# controller.net
KiCad netlist of a schematic drawn in EAGLE
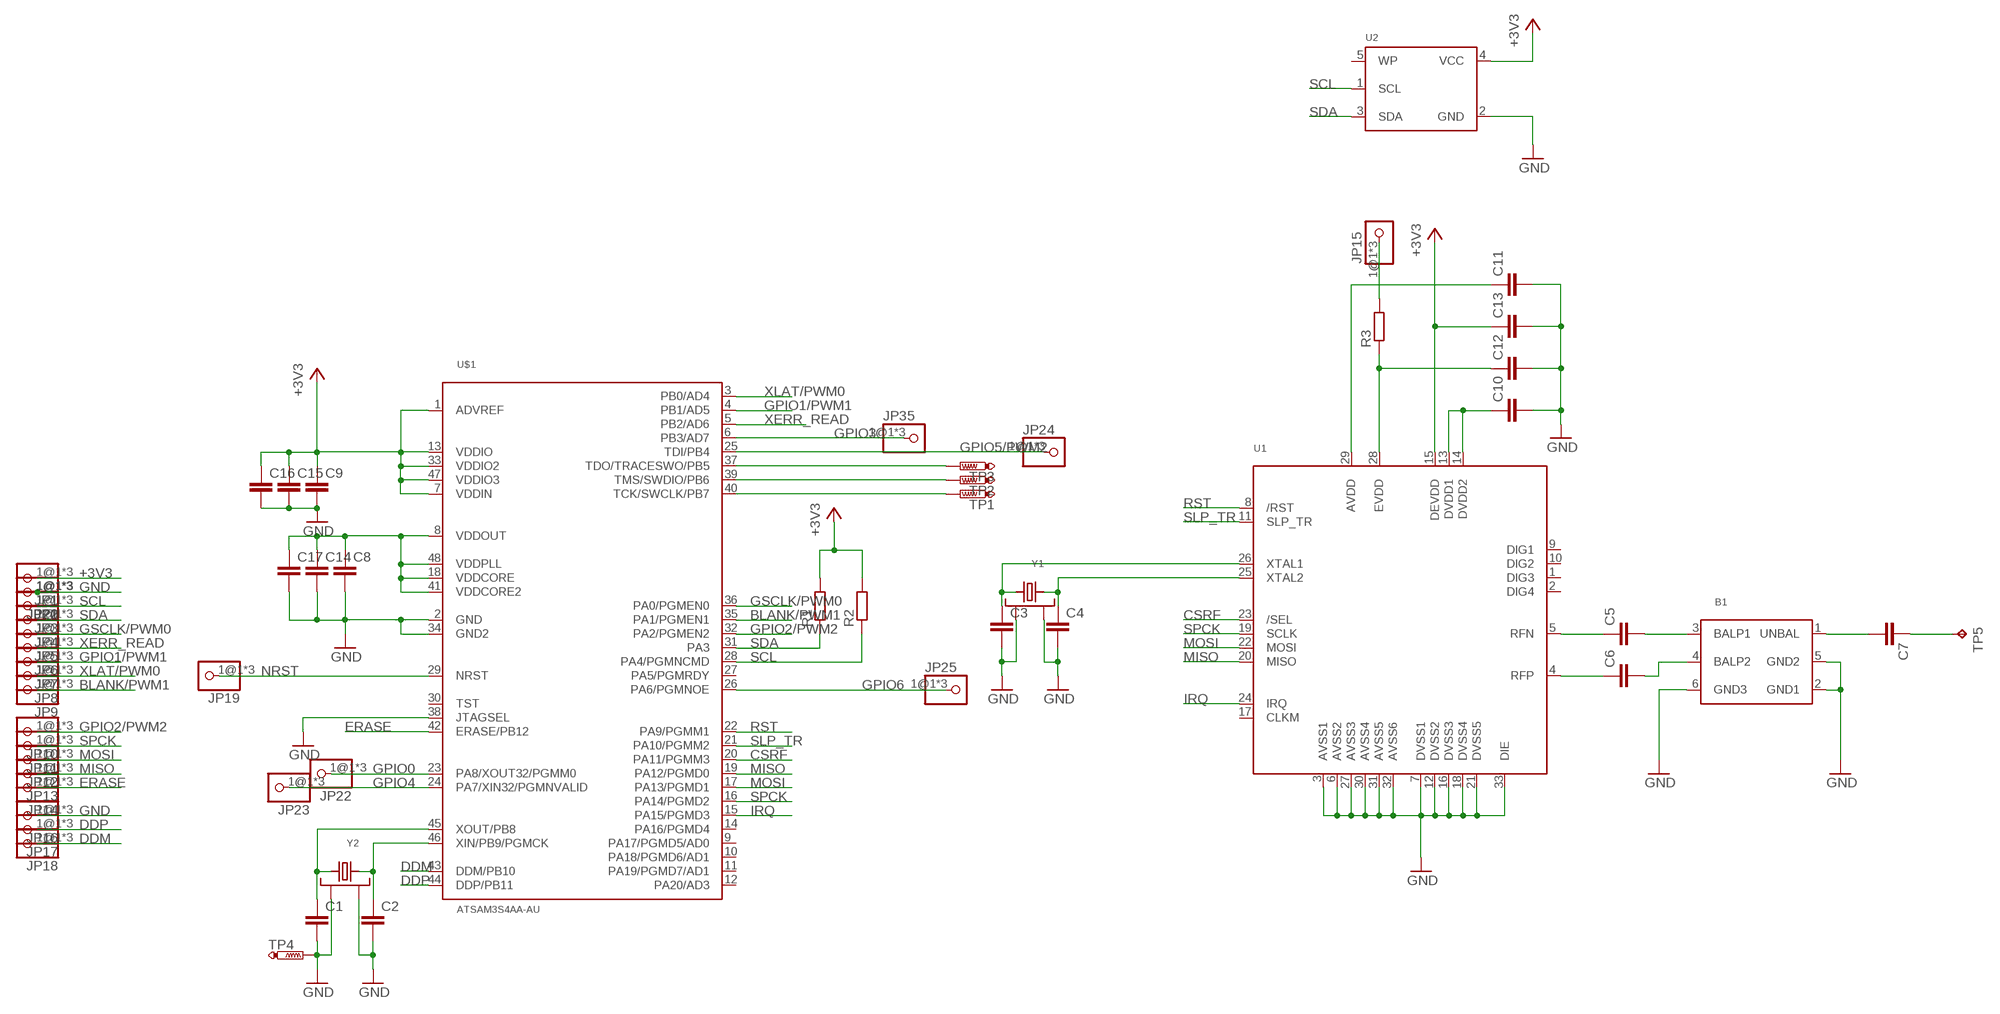
[diagram p0: schematic, sheet 1]

(export (version "E")
  (design (tool "Eeschema 10.0.6"))
  (components
    (comp (ref "B1")
      (value "BALUN+LP")
      (footprint "eagle-import:BALUN0805")
      (libsource (lib "eagle-import") (part "BALUN+LP"))
    )
    (comp (ref "C1")
      (value "C-EUC0402K")
      (footprint "eagle-import:C0402K")
      (libsource (lib "eagle-import") (part "C-EUC0402K"))
    )
    (comp (ref "C2")
      (value "C-EUC0402K")
      (footprint "eagle-import:C0402K")
      (libsource (lib "eagle-import") (part "C-EUC0402K"))
    )
    (comp (ref "C3")
      (value "C-EUC0402K")
      (footprint "eagle-import:C0402K")
      (libsource (lib "eagle-import") (part "C-EUC0402K"))
    )
    (comp (ref "C4")
      (value "C-EUC0402K")
      (footprint "eagle-import:C0402K")
      (libsource (lib "eagle-import") (part "C-EUC0402K"))
    )
    (comp (ref "C5")
      (value "C-EUC0402K")
      (footprint "eagle-import:C0402K")
      (libsource (lib "eagle-import") (part "C-EUC0402K"))
    )
    (comp (ref "C6")
      (value "C-EUC0402K")
      (footprint "eagle-import:C0402K")
      (libsource (lib "eagle-import") (part "C-EUC0402K"))
    )
    (comp (ref "C7")
      (value "C-EUC0402K")
      (footprint "eagle-import:C0402K")
      (libsource (lib "eagle-import") (part "C-EUC0402K"))
    )
    (comp (ref "C8")
      (value "C-EUC0603K")
      (footprint "eagle-import:C0603K")
      (libsource (lib "eagle-import") (part "C-EUC0603K"))
    )
    (comp (ref "C9")
      (value "C-EUC0603K")
      (footprint "eagle-import:C0603K")
      (libsource (lib "eagle-import") (part "C-EUC0603K"))
    )
    (comp (ref "C10")
      (value "C-EUC0603K")
      (footprint "eagle-import:C0603K")
      (libsource (lib "eagle-import") (part "C-EUC0603K"))
    )
    (comp (ref "C11")
      (value "C-EUC0603K")
      (footprint "eagle-import:C0603K")
      (libsource (lib "eagle-import") (part "C-EUC0603K"))
    )
    (comp (ref "C12")
      (value "C-EUC0603K")
      (footprint "eagle-import:C0603K")
      (libsource (lib "eagle-import") (part "C-EUC0603K"))
    )
    (comp (ref "C13")
      (value "C-EUC0603K")
      (footprint "eagle-import:C0603K")
      (libsource (lib "eagle-import") (part "C-EUC0603K"))
    )
    (comp (ref "C14")
      (value "C-EUC0603K")
      (footprint "eagle-import:C0603K")
      (libsource (lib "eagle-import") (part "C-EUC0603K"))
    )
    (comp (ref "C15")
      (value "C-EUC0603K")
      (footprint "eagle-import:C0603K")
      (libsource (lib "eagle-import") (part "C-EUC0603K"))
    )
    (comp (ref "C16")
      (value "C-EUC0603K")
      (footprint "eagle-import:C0603K")
      (libsource (lib "eagle-import") (part "C-EUC0603K"))
    )
    (comp (ref "C17")
      (value "C-EUC0805K")
      (footprint "eagle-import:C0805K")
      (libsource (lib "eagle-import") (part "C-EUC0805K"))
    )
    (comp (ref "JP1")
      (value "HEADER-1X1PAD")
      (footprint "eagle-import:1MMPAD")
      (libsource (lib "eagle-import") (part "HEADER-1X1PAD"))
    )
    (comp (ref "JP2")
      (value "HEADER-1X1PAD")
      (footprint "eagle-import:1MMPAD")
      (libsource (lib "eagle-import") (part "HEADER-1X1PAD"))
    )
    (comp (ref "JP3")
      (value "HEADER-1X1PAD")
      (footprint "eagle-import:1MMPAD")
      (libsource (lib "eagle-import") (part "HEADER-1X1PAD"))
    )
    (comp (ref "JP4")
      (value "HEADER-1X1PAD")
      (footprint "eagle-import:1MMPAD")
      (libsource (lib "eagle-import") (part "HEADER-1X1PAD"))
    )
    (comp (ref "JP5")
      (value "HEADER-1X1PAD")
      (footprint "eagle-import:1MMPAD")
      (libsource (lib "eagle-import") (part "HEADER-1X1PAD"))
    )
    (comp (ref "JP6")
      (value "HEADER-1X1PAD")
      (footprint "eagle-import:1MMPAD")
      (libsource (lib "eagle-import") (part "HEADER-1X1PAD"))
    )
    (comp (ref "JP7")
      (value "HEADER-1X1PAD")
      (footprint "eagle-import:1MMPAD")
      (libsource (lib "eagle-import") (part "HEADER-1X1PAD"))
    )
    (comp (ref "JP8")
      (value "HEADER-1X1PAD")
      (footprint "eagle-import:1MMPAD")
      (libsource (lib "eagle-import") (part "HEADER-1X1PAD"))
    )
    (comp (ref "JP9")
      (value "HEADER-1X1PAD")
      (footprint "eagle-import:1MMPAD")
      (libsource (lib "eagle-import") (part "HEADER-1X1PAD"))
    )
    (comp (ref "JP10")
      (value "HEADER-1X1PAD")
      (footprint "eagle-import:1MMPAD")
      (libsource (lib "eagle-import") (part "HEADER-1X1PAD"))
    )
    (comp (ref "JP11")
      (value "HEADER-1X1PAD")
      (footprint "eagle-import:1MMPAD")
      (libsource (lib "eagle-import") (part "HEADER-1X1PAD"))
    )
    (comp (ref "JP12")
      (value "HEADER-1X1PAD")
      (footprint "eagle-import:1MMPAD")
      (libsource (lib "eagle-import") (part "HEADER-1X1PAD"))
    )
    (comp (ref "JP13")
      (value "HEADER-1X1PAD")
      (footprint "eagle-import:1MMPAD")
      (libsource (lib "eagle-import") (part "HEADER-1X1PAD"))
    )
    (comp (ref "JP14")
      (value "HEADER-1X1PAD")
      (footprint "eagle-import:1MMPAD")
      (libsource (lib "eagle-import") (part "HEADER-1X1PAD"))
    )
    (comp (ref "JP15")
      (value "HEADER-1X1PAD")
      (footprint "eagle-import:1MMPAD")
      (libsource (lib "eagle-import") (part "HEADER-1X1PAD"))
    )
    (comp (ref "JP16")
      (value "HEADER-1X1PAD")
      (footprint "eagle-import:1MMPAD")
      (libsource (lib "eagle-import") (part "HEADER-1X1PAD"))
    )
    (comp (ref "JP17")
      (value "HEADER-1X1PAD")
      (footprint "eagle-import:1MMPAD")
      (libsource (lib "eagle-import") (part "HEADER-1X1PAD"))
    )
    (comp (ref "JP18")
      (value "HEADER-1X1PAD")
      (footprint "eagle-import:1MMPAD")
      (libsource (lib "eagle-import") (part "HEADER-1X1PAD"))
    )
    (comp (ref "JP19")
      (value "HEADER-1X1PAD")
      (footprint "eagle-import:1MMPAD")
      (libsource (lib "eagle-import") (part "HEADER-1X1PAD"))
    )
    (comp (ref "JP20")
      (value "HEADER-1X1PAD")
      (footprint "eagle-import:1MMPAD")
      (libsource (lib "eagle-import") (part "HEADER-1X1PAD"))
    )
    (comp (ref "JP21")
      (value "HEADER-1X1PAD")
      (footprint "eagle-import:1MMPAD")
      (libsource (lib "eagle-import") (part "HEADER-1X1PAD"))
    )
    (comp (ref "JP22")
      (value "HEADER-1X1PAD")
      (footprint "eagle-import:1MMPAD")
      (libsource (lib "eagle-import") (part "HEADER-1X1PAD"))
    )
    (comp (ref "JP23")
      (value "HEADER-1X1PAD")
      (footprint "eagle-import:1MMPAD")
      (libsource (lib "eagle-import") (part "HEADER-1X1PAD"))
    )
    (comp (ref "JP24")
      (value "HEADER-1X1PAD")
      (footprint "eagle-import:1MMPAD")
      (libsource (lib "eagle-import") (part "HEADER-1X1PAD"))
    )
    (comp (ref "JP25")
      (value "HEADER-1X1PAD")
      (footprint "eagle-import:1MMPAD")
      (libsource (lib "eagle-import") (part "HEADER-1X1PAD"))
    )
    (comp (ref "JP35")
      (value "HEADER-1X1PAD")
      (footprint "eagle-import:1MMPAD")
      (libsource (lib "eagle-import") (part "HEADER-1X1PAD"))
    )
    (comp (ref "R1")
      (value "R-EU_R0402")
      (footprint "eagle-import:R0402")
      (libsource (lib "eagle-import") (part "R-EU_R0402"))
    )
    (comp (ref "R2")
      (value "R-EU_R0402")
      (footprint "eagle-import:R0402")
      (libsource (lib "eagle-import") (part "R-EU_R0402"))
    )
    (comp (ref "R3")
      (value "R-EU_R0805")
      (footprint "eagle-import:R0805")
      (libsource (lib "eagle-import") (part "R-EU_R0805"))
    )
    (comp (ref "TP1")
      (value "PTR1TP15R")
      (footprint "eagle-import:TP15R")
      (libsource (lib "eagle-import") (part "PTR1TP15R"))
    )
    (comp (ref "TP2")
      (value "PTR1TP15R")
      (footprint "eagle-import:TP15R")
      (libsource (lib "eagle-import") (part "PTR1TP15R"))
    )
    (comp (ref "TP3")
      (value "PTR1TP15R")
      (footprint "eagle-import:TP15R")
      (libsource (lib "eagle-import") (part "PTR1TP15R"))
    )
    (comp (ref "TP4")
      (value "PTR1TP15R")
      (footprint "eagle-import:TP15R")
      (libsource (lib "eagle-import") (part "PTR1TP15R"))
    )
    (comp (ref "TP5")
      (value "TPTP15SQ")
      (footprint "eagle-import:TP15SQ")
      (libsource (lib "eagle-import") (part "TPTP15SQ"))
    )
    (comp (ref "U$1")
      (value "ATSAM3S4AA-AU")
      (footprint "eagle-import:LQFP48")
      (libsource (lib "eagle-import") (part "ATSAM3S4AA-AU"))
    )
    (comp (ref "U1")
      (value "AT86RF212")
      (footprint "eagle-import:32QN2")
      (libsource (lib "eagle-import") (part "AT86RF212"))
    )
    (comp (ref "U2")
      (value "MCP24AA32")
      (footprint "eagle-import:SOT23-5")
      (libsource (lib "eagle-import") (part "MCP24AA32"))
    )
    (comp (ref "Y1")
      (value "CRYSTALTHIN")
      (footprint "eagle-import:CRYSTAL_3.2X2.5")
      (libsource (lib "eagle-import") (part "CRYSTALTHIN"))
    )
    (comp (ref "Y2")
      (value "CRYSTALTHIN")
      (footprint "eagle-import:CRYSTAL_3.2X2.5")
      (libsource (lib "eagle-import") (part "CRYSTALTHIN"))
    )
  )
  (nets
    (net (code "1") (name "+3V3") (class "Default")
      (node (ref "C13") (pin "1") (pinfunction "1_1") (pintype "passive"))
      (node (ref "C15") (pin "1") (pinfunction "1_1") (pintype "passive"))
      (node (ref "C16") (pin "1") (pinfunction "1_1") (pintype "passive"))
      (node (ref "C9") (pin "1") (pinfunction "1_1") (pintype "passive"))
      (node (ref "JP1") (pin "1@1") (pinfunction "1_1@1") (pintype "passive"))
      (node (ref "JP1") (pin "1@2") (pinfunction "1_1@2") (pintype "passive"))
      (node (ref "JP1") (pin "1@3") (pinfunction "1_1@3") (pintype "passive"))
      (node (ref "R1") (pin "2") (pinfunction "2_2") (pintype "passive"))
      (node (ref "R2") (pin "2") (pinfunction "2_2") (pintype "passive"))
      (node (ref "U$1") (pin "1") (pinfunction "ADVREF_1") (pintype "bidirectional"))
      (node (ref "U$1") (pin "13") (pinfunction "VDDIO_13") (pintype "bidirectional"))
      (node (ref "U$1") (pin "33") (pinfunction "VDDIO2_33") (pintype "bidirectional"))
      (node (ref "U$1") (pin "47") (pinfunction "VDDIO3_47") (pintype "bidirectional"))
      (node (ref "U$1") (pin "7") (pinfunction "VDDIN_7") (pintype "bidirectional"))
      (node (ref "U1") (pin "15") (pinfunction "DEVDD_15") (pintype "bidirectional"))
      (node (ref "U2") (pin "4") (pinfunction "VCC_4") (pintype "bidirectional"))
    )
    (net (code "2") (name "/BLANK{slash}PWM1") (class "Default")
      (node (ref "JP9") (pin "1@1") (pinfunction "1_1@1") (pintype "passive"))
      (node (ref "JP9") (pin "1@2") (pinfunction "1_1@2") (pintype "passive"))
      (node (ref "JP9") (pin "1@3") (pinfunction "1_1@3") (pintype "passive"))
      (node (ref "U$1") (pin "35") (pinfunction "PA1/PGMEN1_35") (pintype "bidirectional"))
    )
    (net (code "3") (name "/CSRF") (class "Default")
      (node (ref "U$1") (pin "20") (pinfunction "PA11/PGMM3_20") (pintype "bidirectional"))
      (node (ref "U1") (pin "23") (pinfunction "/SEL_23") (pintype "bidirectional"))
    )
    (net (code "4") (name "/DDM") (class "Default")
      (node (ref "JP18") (pin "1@1") (pinfunction "1_1@1") (pintype "passive"))
      (node (ref "JP18") (pin "1@2") (pinfunction "1_1@2") (pintype "passive"))
      (node (ref "JP18") (pin "1@3") (pinfunction "1_1@3") (pintype "passive"))
      (node (ref "U$1") (pin "43") (pinfunction "DDM/PB10_43") (pintype "bidirectional"))
    )
    (net (code "5") (name "/DDP") (class "Default")
      (node (ref "JP17") (pin "1@1") (pinfunction "1_1@1") (pintype "passive"))
      (node (ref "JP17") (pin "1@2") (pinfunction "1_1@2") (pintype "passive"))
      (node (ref "JP17") (pin "1@3") (pinfunction "1_1@3") (pintype "passive"))
      (node (ref "U$1") (pin "44") (pinfunction "DDP/PB11_44") (pintype "bidirectional"))
    )
    (net (code "6") (name "/ERASE") (class "Default")
      (node (ref "JP14") (pin "1@1") (pinfunction "1_1@1") (pintype "passive"))
      (node (ref "JP14") (pin "1@2") (pinfunction "1_1@2") (pintype "passive"))
      (node (ref "JP14") (pin "1@3") (pinfunction "1_1@3") (pintype "passive"))
      (node (ref "U$1") (pin "42") (pinfunction "ERASE/PB12_42") (pintype "bidirectional"))
    )
    (net (code "7") (name "/GPIO0") (class "Default")
      (node (ref "JP22") (pin "1@1") (pinfunction "1_1@1") (pintype "passive"))
      (node (ref "JP22") (pin "1@2") (pinfunction "1_1@2") (pintype "passive"))
      (node (ref "JP22") (pin "1@3") (pinfunction "1_1@3") (pintype "passive"))
      (node (ref "U$1") (pin "23") (pinfunction "PA8/XOUT32/PGMM0_23") (pintype "bidirectional"))
    )
    (net (code "8") (name "/GPIO1{slash}PWM1") (class "Default")
      (node (ref "JP7") (pin "1@1") (pinfunction "1_1@1") (pintype "passive"))
      (node (ref "JP7") (pin "1@2") (pinfunction "1_1@2") (pintype "passive"))
      (node (ref "JP7") (pin "1@3") (pinfunction "1_1@3") (pintype "passive"))
      (node (ref "U$1") (pin "4") (pinfunction "PB1/AD5_4") (pintype "bidirectional"))
    )
    (net (code "9") (name "/GPIO2{slash}PWM2") (class "Default")
      (node (ref "JP10") (pin "1@1") (pinfunction "1_1@1") (pintype "passive"))
      (node (ref "JP10") (pin "1@2") (pinfunction "1_1@2") (pintype "passive"))
      (node (ref "JP10") (pin "1@3") (pinfunction "1_1@3") (pintype "passive"))
      (node (ref "U$1") (pin "32") (pinfunction "PA2/PGMEN2_32") (pintype "bidirectional"))
    )
    (net (code "10") (name "/GPIO3") (class "Default")
      (node (ref "JP35") (pin "1@1") (pinfunction "1_1@1") (pintype "passive"))
      (node (ref "JP35") (pin "1@2") (pinfunction "1_1@2") (pintype "passive"))
      (node (ref "JP35") (pin "1@3") (pinfunction "1_1@3") (pintype "passive"))
      (node (ref "U$1") (pin "6") (pinfunction "PB3/AD7_6") (pintype "bidirectional"))
    )
    (net (code "11") (name "/GPIO4") (class "Default")
      (node (ref "JP23") (pin "1@1") (pinfunction "1_1@1") (pintype "passive"))
      (node (ref "JP23") (pin "1@2") (pinfunction "1_1@2") (pintype "passive"))
      (node (ref "JP23") (pin "1@3") (pinfunction "1_1@3") (pintype "passive"))
      (node (ref "U$1") (pin "24") (pinfunction "PA7/XIN32/PGMNVALID_24") (pintype "bidirectional"))
    )
    (net (code "12") (name "/GPIO5{slash}PWM2") (class "Default")
      (node (ref "JP24") (pin "1@1") (pinfunction "1_1@1") (pintype "passive"))
      (node (ref "JP24") (pin "1@2") (pinfunction "1_1@2") (pintype "passive"))
      (node (ref "JP24") (pin "1@3") (pinfunction "1_1@3") (pintype "passive"))
      (node (ref "U$1") (pin "25") (pinfunction "TDI/PB4_25") (pintype "bidirectional"))
    )
    (net (code "13") (name "/GPIO6") (class "Default")
      (node (ref "JP25") (pin "1@1") (pinfunction "1_1@1") (pintype "passive"))
      (node (ref "JP25") (pin "1@2") (pinfunction "1_1@2") (pintype "passive"))
      (node (ref "JP25") (pin "1@3") (pinfunction "1_1@3") (pintype "passive"))
      (node (ref "U$1") (pin "26") (pinfunction "PA6/PGMNOE_26") (pintype "bidirectional"))
    )
    (net (code "14") (name "/GSCLK{slash}PWM0") (class "Default")
      (node (ref "JP5") (pin "1@1") (pinfunction "1_1@1") (pintype "passive"))
      (node (ref "JP5") (pin "1@2") (pinfunction "1_1@2") (pintype "passive"))
      (node (ref "JP5") (pin "1@3") (pinfunction "1_1@3") (pintype "passive"))
      (node (ref "U$1") (pin "36") (pinfunction "PA0/PGMEN0_36") (pintype "bidirectional"))
    )
    (net (code "15") (name "/IRQ") (class "Default")
      (node (ref "U$1") (pin "15") (pinfunction "PA15/PGMD3_15") (pintype "bidirectional"))
      (node (ref "U1") (pin "24") (pinfunction "IRQ_24") (pintype "bidirectional"))
    )
    (net (code "16") (name "/MISO") (class "Default")
      (node (ref "JP13") (pin "1@1") (pinfunction "1_1@1") (pintype "passive"))
      (node (ref "JP13") (pin "1@2") (pinfunction "1_1@2") (pintype "passive"))
      (node (ref "JP13") (pin "1@3") (pinfunction "1_1@3") (pintype "passive"))
      (node (ref "U$1") (pin "19") (pinfunction "PA12/PGMD0_19") (pintype "bidirectional"))
      (node (ref "U1") (pin "20") (pinfunction "MISO_20") (pintype "bidirectional"))
    )
    (net (code "17") (name "/MOSI") (class "Default")
      (node (ref "JP12") (pin "1@1") (pinfunction "1_1@1") (pintype "passive"))
      (node (ref "JP12") (pin "1@2") (pinfunction "1_1@2") (pintype "passive"))
      (node (ref "JP12") (pin "1@3") (pinfunction "1_1@3") (pintype "passive"))
      (node (ref "U$1") (pin "17") (pinfunction "PA13/PGMD1_17") (pintype "bidirectional"))
      (node (ref "U1") (pin "22") (pinfunction "MOSI_22") (pintype "bidirectional"))
    )
    (net (code "18") (name "/NRST") (class "Default")
      (node (ref "JP19") (pin "1@1") (pinfunction "1_1@1") (pintype "passive"))
      (node (ref "JP19") (pin "1@2") (pinfunction "1_1@2") (pintype "passive"))
      (node (ref "JP19") (pin "1@3") (pinfunction "1_1@3") (pintype "passive"))
      (node (ref "U$1") (pin "29") (pinfunction "NRST_29") (pintype "bidirectional"))
    )
    (net (code "19") (name "/RST") (class "Default")
      (node (ref "U$1") (pin "22") (pinfunction "PA9/PGMM1_22") (pintype "bidirectional"))
      (node (ref "U1") (pin "8") (pinfunction "/RST_8") (pintype "bidirectional"))
    )
    (net (code "20") (name "/SCL") (class "Default")
      (node (ref "JP3") (pin "1@1") (pinfunction "1_1@1") (pintype "passive"))
      (node (ref "JP3") (pin "1@2") (pinfunction "1_1@2") (pintype "passive"))
      (node (ref "JP3") (pin "1@3") (pinfunction "1_1@3") (pintype "passive"))
      (node (ref "R2") (pin "1") (pinfunction "1_1") (pintype "passive"))
      (node (ref "U$1") (pin "28") (pinfunction "PA4/PGMNCMD_28") (pintype "bidirectional"))
      (node (ref "U2") (pin "1") (pinfunction "SCL_1") (pintype "bidirectional"))
    )
    (net (code "21") (name "/SDA") (class "Default")
      (node (ref "JP4") (pin "1@1") (pinfunction "1_1@1") (pintype "passive"))
      (node (ref "JP4") (pin "1@2") (pinfunction "1_1@2") (pintype "passive"))
      (node (ref "JP4") (pin "1@3") (pinfunction "1_1@3") (pintype "passive"))
      (node (ref "R1") (pin "1") (pinfunction "1_1") (pintype "passive"))
      (node (ref "U$1") (pin "31") (pinfunction "PA3_31") (pintype "bidirectional"))
      (node (ref "U2") (pin "3") (pinfunction "SDA_3") (pintype "bidirectional"))
    )
    (net (code "22") (name "/SLP_TR") (class "Default")
      (node (ref "U$1") (pin "21") (pinfunction "PA10/PGMM2_21") (pintype "bidirectional"))
      (node (ref "U1") (pin "11") (pinfunction "SLP_TR_11") (pintype "bidirectional"))
    )
    (net (code "23") (name "/SPCK") (class "Default")
      (node (ref "JP11") (pin "1@1") (pinfunction "1_1@1") (pintype "passive"))
      (node (ref "JP11") (pin "1@2") (pinfunction "1_1@2") (pintype "passive"))
      (node (ref "JP11") (pin "1@3") (pinfunction "1_1@3") (pintype "passive"))
      (node (ref "U$1") (pin "16") (pinfunction "PA14/PGMD2_16") (pintype "bidirectional"))
      (node (ref "U1") (pin "19") (pinfunction "SCLK_19") (pintype "bidirectional"))
    )
    (net (code "24") (name "/XERR_READ") (class "Default")
      (node (ref "JP6") (pin "1@1") (pinfunction "1_1@1") (pintype "passive"))
      (node (ref "JP6") (pin "1@2") (pinfunction "1_1@2") (pintype "passive"))
      (node (ref "JP6") (pin "1@3") (pinfunction "1_1@3") (pintype "passive"))
      (node (ref "U$1") (pin "5") (pinfunction "PB2/AD6_5") (pintype "bidirectional"))
    )
    (net (code "25") (name "/XLAT{slash}PWM0") (class "Default")
      (node (ref "JP8") (pin "1@1") (pinfunction "1_1@1") (pintype "passive"))
      (node (ref "JP8") (pin "1@2") (pinfunction "1_1@2") (pintype "passive"))
      (node (ref "JP8") (pin "1@3") (pinfunction "1_1@3") (pintype "passive"))
      (node (ref "U$1") (pin "3") (pinfunction "PB0/AD4_3") (pintype "bidirectional"))
    )
    (net (code "26") (name "GND") (class "Default")
      (node (ref "B1") (pin "2") (pinfunction "GND1_2") (pintype "bidirectional"))
      (node (ref "B1") (pin "5") (pinfunction "GND2_5") (pintype "bidirectional"))
      (node (ref "B1") (pin "6") (pinfunction "GND3_6") (pintype "bidirectional"))
      (node (ref "C1") (pin "2") (pinfunction "2_2") (pintype "passive"))
      (node (ref "C10") (pin "2") (pinfunction "2_2") (pintype "passive"))
      (node (ref "C11") (pin "2") (pinfunction "2_2") (pintype "passive"))
      (node (ref "C12") (pin "2") (pinfunction "2_2") (pintype "passive"))
      (node (ref "C13") (pin "2") (pinfunction "2_2") (pintype "passive"))
      (node (ref "C14") (pin "2") (pinfunction "2_2") (pintype "passive"))
      (node (ref "C15") (pin "2") (pinfunction "2_2") (pintype "passive"))
      (node (ref "C16") (pin "2") (pinfunction "2_2") (pintype "passive"))
      (node (ref "C17") (pin "2") (pinfunction "2_2") (pintype "passive"))
      (node (ref "C2") (pin "2") (pinfunction "2_2") (pintype "passive"))
      (node (ref "C3") (pin "2") (pinfunction "2_2") (pintype "passive"))
      (node (ref "C4") (pin "2") (pinfunction "2_2") (pintype "passive"))
      (node (ref "C8") (pin "2") (pinfunction "2_2") (pintype "passive"))
      (node (ref "C9") (pin "2") (pinfunction "2_2") (pintype "passive"))
      (node (ref "JP16") (pin "1@1") (pinfunction "1_1@1") (pintype "passive"))
      (node (ref "JP16") (pin "1@2") (pinfunction "1_1@2") (pintype "passive"))
      (node (ref "JP16") (pin "1@3") (pinfunction "1_1@3") (pintype "passive"))
      (node (ref "JP2") (pin "1@1") (pinfunction "1_1@1") (pintype "passive"))
      (node (ref "JP2") (pin "1@2") (pinfunction "1_1@2") (pintype "passive"))
      (node (ref "JP2") (pin "1@3") (pinfunction "1_1@3") (pintype "passive"))
      (node (ref "JP20") (pin "1@1") (pinfunction "1_1@1") (pintype "passive"))
      (node (ref "JP20") (pin "1@2") (pinfunction "1_1@2") (pintype "passive"))
      (node (ref "JP20") (pin "1@3") (pinfunction "1_1@3") (pintype "passive"))
      (node (ref "JP21") (pin "1@1") (pinfunction "1_1@1") (pintype "passive"))
      (node (ref "JP21") (pin "1@2") (pinfunction "1_1@2") (pintype "passive"))
      (node (ref "JP21") (pin "1@3") (pinfunction "1_1@3") (pintype "passive"))
      (node (ref "TP4") (pin "TP") (pinfunction "TP_TP") (pintype "input"))
      (node (ref "U$1") (pin "2") (pinfunction "GND_2") (pintype "bidirectional"))
      (node (ref "U$1") (pin "34") (pinfunction "GND2_34") (pintype "bidirectional"))
      (node (ref "U$1") (pin "38") (pinfunction "JTAGSEL_38") (pintype "bidirectional"))
      (node (ref "U1") (pin "12") (pinfunction "DVSS2_12") (pintype "bidirectional"))
      (node (ref "U1") (pin "16") (pinfunction "DVSS3_16") (pintype "bidirectional"))
      (node (ref "U1") (pin "18") (pinfunction "DVSS4_18") (pintype "bidirectional"))
      (node (ref "U1") (pin "21") (pinfunction "DVSS5_21") (pintype "bidirectional"))
      (node (ref "U1") (pin "27") (pinfunction "AVSS3_27") (pintype "bidirectional"))
      (node (ref "U1") (pin "3") (pinfunction "AVSS1_3") (pintype "bidirectional"))
      (node (ref "U1") (pin "30") (pinfunction "AVSS4_30") (pintype "bidirectional"))
      (node (ref "U1") (pin "31") (pinfunction "AVSS5_31") (pintype "bidirectional"))
      (node (ref "U1") (pin "32") (pinfunction "AVSS6_32") (pintype "bidirectional"))
      (node (ref "U1") (pin "33") (pinfunction "DIE_33") (pintype "bidirectional"))
      (node (ref "U1") (pin "6") (pinfunction "AVSS2_6") (pintype "bidirectional"))
      (node (ref "U1") (pin "7") (pinfunction "DVSS1_7") (pintype "bidirectional"))
      (node (ref "U2") (pin "2") (pinfunction "GND_2") (pintype "bidirectional"))
      (node (ref "Y1") (pin "GND1") (pinfunction "GND1_GND1") (pintype "bidirectional"))
      (node (ref "Y1") (pin "GND2") (pinfunction "GND2_GND2") (pintype "bidirectional"))
      (node (ref "Y2") (pin "GND1") (pinfunction "GND1_GND1") (pintype "bidirectional"))
      (node (ref "Y2") (pin "GND2") (pinfunction "GND2_GND2") (pintype "bidirectional"))
    )
    (net (code "27") (name "Net-(B1-BALP1)") (class "Default")
      (node (ref "B1") (pin "3") (pinfunction "BALP1_3") (pintype "bidirectional"))
      (node (ref "C5") (pin "2") (pinfunction "2_2") (pintype "passive"))
    )
    (net (code "28") (name "Net-(B1-BALP2)") (class "Default")
      (node (ref "B1") (pin "4") (pinfunction "BALP2_4") (pintype "bidirectional"))
      (node (ref "C6") (pin "2") (pinfunction "2_2") (pintype "passive"))
    )
    (net (code "29") (name "Net-(B1-UNBAL)") (class "Default")
      (node (ref "B1") (pin "1") (pinfunction "UNBAL_1") (pintype "bidirectional"))
      (node (ref "C7") (pin "2") (pinfunction "2_2") (pintype "passive"))
    )
    (net (code "30") (name "Net-(C7-Pad1)") (class "Default")
      (node (ref "C7") (pin "1") (pinfunction "1_1") (pintype "passive"))
      (node (ref "TP5") (pin "TP") (pinfunction "TP_TP") (pintype "input"))
    )
    (net (code "31") (name "Net-(JP15-1-Pad1@1)") (class "Default")
      (node (ref "JP15") (pin "1@1") (pinfunction "1_1@1") (pintype "passive"))
      (node (ref "JP15") (pin "1@2") (pinfunction "1_1@2") (pintype "passive"))
      (node (ref "JP15") (pin "1@3") (pinfunction "1_1@3") (pintype "passive"))
      (node (ref "R3") (pin "2") (pinfunction "2_2") (pintype "passive"))
    )
    (net (code "32") (name "Net-(U$1-TCK{slash}SWCLK{slash}PB7)") (class "Default")
      (node (ref "TP1") (pin "TP") (pinfunction "TP_TP") (pintype "input"))
      (node (ref "U$1") (pin "40") (pinfunction "TCK/SWCLK/PB7_40") (pintype "bidirectional"))
    )
    (net (code "33") (name "Net-(U$1-TDO{slash}TRACESWO{slash}PB5)") (class "Default")
      (node (ref "TP3") (pin "TP") (pinfunction "TP_TP") (pintype "input"))
      (node (ref "U$1") (pin "37") (pinfunction "TDO/TRACESWO/PB5_37") (pintype "bidirectional"))
    )
    (net (code "34") (name "Net-(U$1-TMS{slash}SWDIO{slash}PB6)") (class "Default")
      (node (ref "TP2") (pin "TP") (pinfunction "TP_TP") (pintype "input"))
      (node (ref "U$1") (pin "39") (pinfunction "TMS/SWDIO/PB6_39") (pintype "bidirectional"))
    )
    (net (code "35") (name "Net-(U$1-VDDCORE)") (class "Default")
      (node (ref "C14") (pin "1") (pinfunction "1_1") (pintype "passive"))
      (node (ref "C17") (pin "1") (pinfunction "1_1") (pintype "passive"))
      (node (ref "C8") (pin "1") (pinfunction "1_1") (pintype "passive"))
      (node (ref "U$1") (pin "18") (pinfunction "VDDCORE_18") (pintype "bidirectional"))
      (node (ref "U$1") (pin "41") (pinfunction "VDDCORE2_41") (pintype "bidirectional"))
      (node (ref "U$1") (pin "48") (pinfunction "VDDPLL_48") (pintype "bidirectional"))
      (node (ref "U$1") (pin "8") (pinfunction "VDDOUT_8") (pintype "bidirectional"))
    )
    (net (code "36") (name "Net-(U$1-XIN{slash}PB9{slash}PGMCK)") (class "Default")
      (node (ref "C2") (pin "1") (pinfunction "1_1") (pintype "passive"))
      (node (ref "U$1") (pin "46") (pinfunction "XIN/PB9/PGMCK_46") (pintype "bidirectional"))
      (node (ref "Y2") (pin "1") (pinfunction "1_1") (pintype "passive"))
    )
    (net (code "37") (name "Net-(U$1-XOUT{slash}PB8)") (class "Default")
      (node (ref "C1") (pin "1") (pinfunction "1_1") (pintype "passive"))
      (node (ref "U$1") (pin "45") (pinfunction "XOUT/PB8_45") (pintype "bidirectional"))
      (node (ref "Y2") (pin "2") (pinfunction "2_2") (pintype "passive"))
    )
    (net (code "38") (name "Net-(U1-AVDD)") (class "Default")
      (node (ref "C11") (pin "1") (pinfunction "1_1") (pintype "passive"))
      (node (ref "U1") (pin "29") (pinfunction "AVDD_29") (pintype "bidirectional"))
    )
    (net (code "39") (name "Net-(U1-DVDD1)") (class "Default")
      (node (ref "C10") (pin "1") (pinfunction "1_1") (pintype "passive"))
      (node (ref "U1") (pin "13") (pinfunction "DVDD1_13") (pintype "bidirectional"))
      (node (ref "U1") (pin "14") (pinfunction "DVDD2_14") (pintype "bidirectional"))
    )
    (net (code "40") (name "Net-(U1-EVDD)") (class "Default")
      (node (ref "C12") (pin "1") (pinfunction "1_1") (pintype "passive"))
      (node (ref "R3") (pin "1") (pinfunction "1_1") (pintype "passive"))
      (node (ref "U1") (pin "28") (pinfunction "EVDD_28") (pintype "bidirectional"))
    )
    (net (code "41") (name "Net-(U1-RFN)") (class "Default")
      (node (ref "C5") (pin "1") (pinfunction "1_1") (pintype "passive"))
      (node (ref "U1") (pin "5") (pinfunction "RFN_5") (pintype "bidirectional"))
    )
    (net (code "42") (name "Net-(U1-RFP)") (class "Default")
      (node (ref "C6") (pin "1") (pinfunction "1_1") (pintype "passive"))
      (node (ref "U1") (pin "4") (pinfunction "RFP_4") (pintype "bidirectional"))
    )
    (net (code "43") (name "Net-(U1-XTAL1)") (class "Default")
      (node (ref "C3") (pin "1") (pinfunction "1_1") (pintype "passive"))
      (node (ref "U1") (pin "26") (pinfunction "XTAL1_26") (pintype "bidirectional"))
      (node (ref "Y1") (pin "2") (pinfunction "2_2") (pintype "passive"))
    )
    (net (code "44") (name "Net-(U1-XTAL2)") (class "Default")
      (node (ref "C4") (pin "1") (pinfunction "1_1") (pintype "passive"))
      (node (ref "U1") (pin "25") (pinfunction "XTAL2_25") (pintype "bidirectional"))
      (node (ref "Y1") (pin "1") (pinfunction "1_1") (pintype "passive"))
    )
    (net (code "45") (name "unconnected-(U$1-PA5{slash}PGMRDY-Pad27)") (class "Default")
      (node (ref "U$1") (pin "27") (pinfunction "PA5/PGMRDY_27") (pintype "bidirectional"))
    )
    (net (code "46") (name "unconnected-(U$1-PA16{slash}PGMD4-Pad14)") (class "Default")
      (node (ref "U$1") (pin "14") (pinfunction "PA16/PGMD4_14") (pintype "bidirectional"))
    )
    (net (code "47") (name "unconnected-(U$1-PA17{slash}PGMD5{slash}AD0-Pad9)") (class "Default")
      (node (ref "U$1") (pin "9") (pinfunction "PA17/PGMD5/AD0_9") (pintype "bidirectional"))
    )
    (net (code "48") (name "unconnected-(U$1-PA18{slash}PGMD6{slash}AD1-Pad10)") (class "Default")
      (node (ref "U$1") (pin "10") (pinfunction "PA18/PGMD6/AD1_10") (pintype "bidirectional"))
    )
    (net (code "49") (name "unconnected-(U$1-PA19{slash}PGMD7{slash}AD1-Pad11)") (class "Default")
      (node (ref "U$1") (pin "11") (pinfunction "PA19/PGMD7/AD1_11") (pintype "bidirectional"))
    )
    (net (code "50") (name "unconnected-(U$1-PA20{slash}AD3-Pad12)") (class "Default")
      (node (ref "U$1") (pin "12") (pinfunction "PA20/AD3_12") (pintype "bidirectional"))
    )
    (net (code "51") (name "unconnected-(U$1-TST-Pad30)") (class "Default")
      (node (ref "U$1") (pin "30") (pinfunction "TST_30") (pintype "bidirectional"))
    )
    (net (code "52") (name "unconnected-(U1-CLKM-Pad17)") (class "Default")
      (node (ref "U1") (pin "17") (pinfunction "CLKM_17") (pintype "bidirectional"))
    )
    (net (code "53") (name "unconnected-(U1-DIG1-Pad9)") (class "Default")
      (node (ref "U1") (pin "9") (pinfunction "DIG1_9") (pintype "bidirectional"))
    )
    (net (code "54") (name "unconnected-(U1-DIG2-Pad10)") (class "Default")
      (node (ref "U1") (pin "10") (pinfunction "DIG2_10") (pintype "bidirectional"))
    )
    (net (code "55") (name "unconnected-(U1-DIG3-Pad1)") (class "Default")
      (node (ref "U1") (pin "1") (pinfunction "DIG3_1") (pintype "bidirectional"))
    )
    (net (code "56") (name "unconnected-(U1-DIG4-Pad2)") (class "Default")
      (node (ref "U1") (pin "2") (pinfunction "DIG4_2") (pintype "bidirectional"))
    )
    (net (code "57") (name "unconnected-(U2-WP-Pad5)") (class "Default")
      (node (ref "U2") (pin "5") (pinfunction "WP_5") (pintype "bidirectional"))
    )
  )
)
